# PG13__REGS_MANAGER.net
KiCad netlist of a schematic drawn in Altium Designer
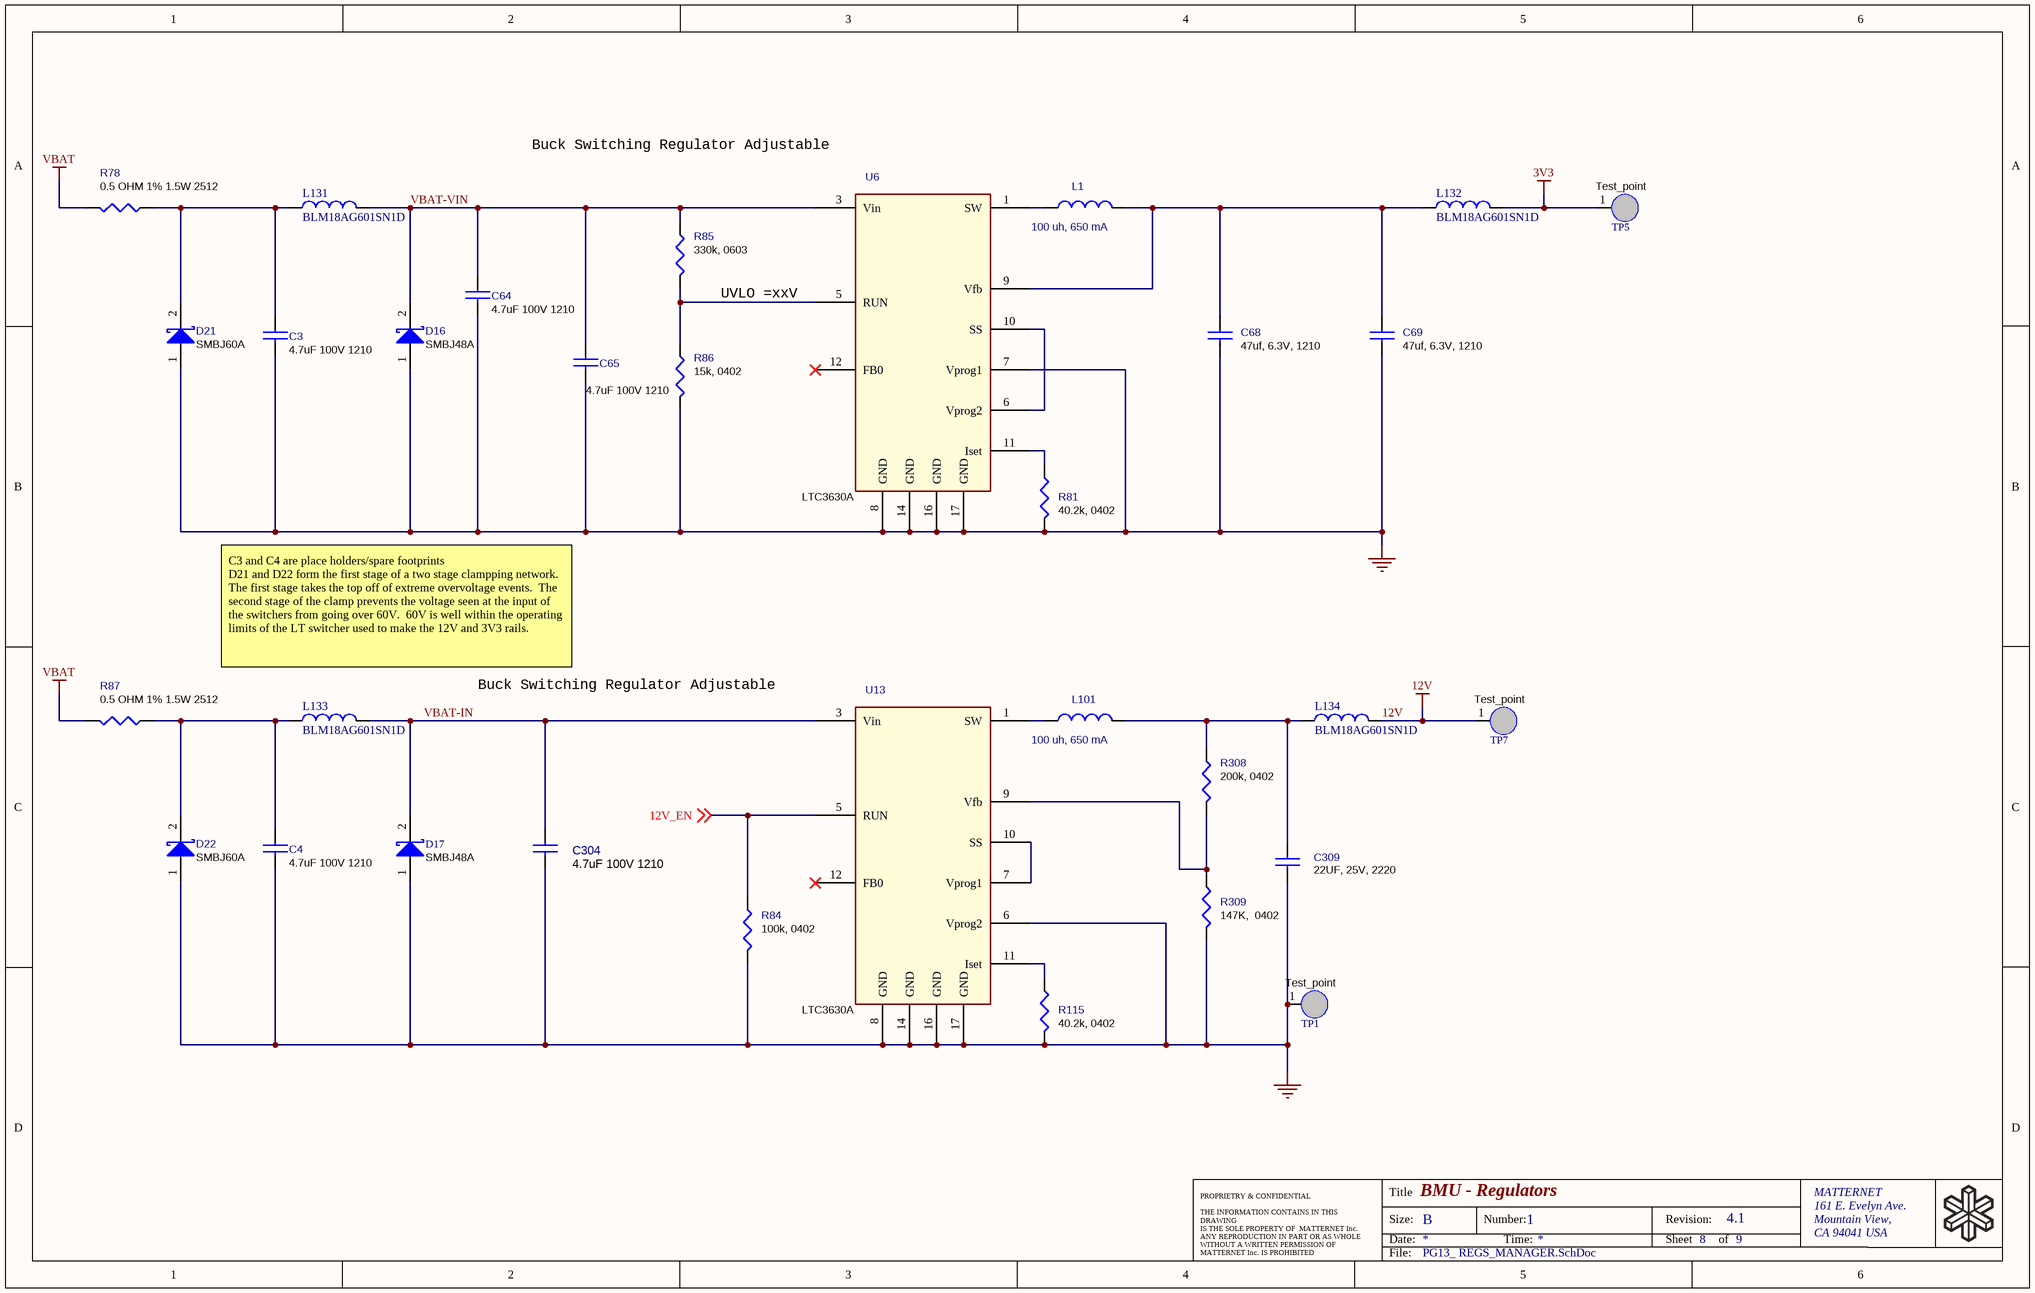
[diagram p0: PG13_ REGS_MANAGER.SchDoc]

(export (version "E")
  (design (tool "Eeschema 10.0.6"))
  (components
    (comp (ref "C3")
      (value "4.7uF 100V 1210")
      (footprint "C1210")
      (description "CAP CER 4.7UF 100V 10% X7S 1210")
      (fields
        (field (name "MANUFACTURER") "TDK")
        (field (name "MANUFACTURER PART NUMBER") "CGA6M3X7S2A475K200AE")
      )
      (libsource (lib "*") (part "CAP-GENERIC"))
    )
    (comp (ref "C4")
      (value "4.7uF 100V 1210")
      (footprint "C1210")
      (description "CAP CER 4.7UF 100V 10% X7S 1210")
      (fields
        (field (name "MANUFACTURER") "TDK")
        (field (name "MANUFACTURER PART NUMBER") "CGA6M3X7S2A475K200AE")
      )
      (libsource (lib "*") (part "CAP-GENERIC"))
    )
    (comp (ref "C64")
      (value "4.7uF 100V 1210")
      (footprint "C1210")
      (description "CAP CER 4.7UF 100V 10% X7S 1210")
      (fields
        (field (name "MANUFACTURER") "TDK")
        (field (name "MANUFACTURER PART NUMBER") "CGA6M3X7S2A475K200AE")
      )
      (libsource (lib "*") (part "CAP-GENERIC"))
    )
    (comp (ref "C65")
      (value "4.7uF 100V 1210")
      (footprint "C1210")
      (description "CAP CER 4.7UF 100V 10% X7S 1210")
      (fields
        (field (name "MANUFACTURER") "TDK")
        (field (name "MANUFACTURER PART NUMBER") "CGA6M3X7S2A475K200AE")
      )
      (libsource (lib "*") (part "CAP-GENERIC"))
    )
    (comp (ref "C68")
      (value "47uf, 6.3V, 1210")
      (footprint "C1210_N")
      (description "CAP CER 47UF 6.3V X7R 1210")
      (fields
        (field (name "MANUFACTURER") "Murata")
        (field (name "MANUFACTURER PART NUMBER") "GCJ32ER70J476KE01L")
      )
      (libsource (lib "*") (part "CAP-Generic-1206"))
    )
    (comp (ref "C69")
      (value "47uf, 6.3V, 1210")
      (footprint "C1210_N")
      (description "CAP CER 47UF 6.3V X7R 1210")
      (fields
        (field (name "MANUFACTURER") "Murata")
        (field (name "MANUFACTURER PART NUMBER") "GCJ32ER70J476KE01L")
      )
      (libsource (lib "*") (part "CAP-Generic-1206"))
    )
    (comp (ref "C304")
      (value "4.7uF 100V 1210")
      (footprint "C1210")
      (description "CAP CER 4.7UF 100V 10% X7S 1210")
      (fields
        (field (name "MANUFACTURER") "TDK")
        (field (name "MANUFACTURER PART NUMBER") "CGA6M3X7S2A475K200AE")
      )
      (libsource (lib "*") (part "CAP-GENERIC"))
    )
    (comp (ref "C309")
      (value "22UF, 25V, 2220")
      (footprint "C2220")
      (description "CAP CER 22UF 25V 10% X7R 2220")
      (fields
        (field (name "MANUFACTURER") "KEMET")
        (field (name "MANUFACTURER PART NUMBER") "C2220X226K3RACAUTO")
      )
      (libsource (lib "*") (part "CAP-GENERIC"))
    )
    (comp (ref "D16")
      (value "SMBJ48A")
      (footprint "DO-214AA")
      (description "Diode TVS Single Uni-Directional 48V 600W 2-Pin DO-214AA")
      (libsource (lib "M2_V8_BMU_V1.0") (part "SMBJ60A"))
    )
    (comp (ref "D17")
      (value "SMBJ48A")
      (footprint "DO-214AA")
      (description "Diode TVS Single Uni-Directional 48V 600W 2-Pin DO-214AA")
      (libsource (lib "M2_V8_BMU_V1.0") (part "SMBJ60A"))
    )
    (comp (ref "D21")
      (value "SMBJ60A")
      (footprint "DO-214AA")
      (libsource (lib "M2_V8_BMU_V1.0") (part "SMBJ60A"))
    )
    (comp (ref "D22")
      (value "SMBJ60A")
      (footprint "DO-214AA")
      (fields
        (field (name "MANUFACTURER") "Vishay Semiconductors")
        (field (name "MANUFACTURER PART NUMBER") "SMBJ60A-E3/52")
      )
      (libsource (lib "M2_V8_BMU_V1.0") (part "SMBJ60A"))
    )
    (comp (ref "L1")
      (value "100 uh, 650 mA")
      (footprint "IND_SRR7045")
      (description "FIXED IND 100UH 650MA 300 MOHM")
      (fields (field (name "MANUFACTURER") "Bourns") (field (name "MANUFACTURER PART NUMBER") "SRR7045-101M"))
      (libsource (lib "*") (part "IND-GENERIC"))
    )
    (comp (ref "L101")
      (value "100 uh, 650 mA")
      (footprint "IND_SRR7045")
      (description "FIXED IND 100UH 650MA 300 MOHM")
      (fields (field (name "MANUFACTURER") "Bourns") (field (name "MANUFACTURER PART NUMBER") "SRR7045-101M"))
      (libsource (lib "*") (part "IND-GENERIC"))
    )
    (comp (ref "L131")
      (value "BLM18AG601SN1D")
      (footprint "INDC1608X10N")
      (description "FERRITE BEAD 600 OHM 0603 1LN")
      (libsource (lib "Altium") (part "BLM18AG601SN1D"))
    )
    (comp (ref "L132")
      (value "BLM18AG601SN1D")
      (footprint "INDC1608X10N")
      (description "FERRITE BEAD 600 OHM 0603 1LN")
      (libsource (lib "Altium") (part "BLM18AG601SN1D"))
    )
    (comp (ref "L133")
      (value "BLM18AG601SN1D")
      (footprint "INDC1608X10N")
      (description "FERRITE BEAD 600 OHM 0603 1LN")
      (libsource (lib "Altium") (part "BLM18AG601SN1D"))
    )
    (comp (ref "L134")
      (value "BLM18AG601SN1D")
      (footprint "INDC1608X10N")
      (description "FERRITE BEAD 600 OHM 0603 1LN")
      (libsource (lib "Altium") (part "BLM18AG601SN1D"))
    )
    (comp (ref "R78")
      (value "0.5 OHM 1% 1.5W 2512")
      (footprint "2512")
      (fields (field (name "TOLERANCE") "1%"))
      (libsource (lib "*") (part "R-Generic"))
    )
    (comp (ref "R81")
      (value "40.2k, 0402")
      (footprint "R0402")
      (description "RES SMD 40.2K OHM 1% 1/16W 0402")
      (fields
        (field (name "MANUFACTURER") "Yageo")
        (field (name "MANUFACTURER PART NUMBER") "RC0402FR-0740K2L")
      )
      (libsource (lib "*") (part "R-Generic-0402"))
    )
    (comp (ref "R84")
      (value "100k, 0402")
      (footprint "R0402")
      (description "RES SMD 100K OHM 1% 1/16W 0402")
      (fields
        (field (name "MANUFACTURER") "Yageo")
        (field (name "MANUFACTURER PART NUMBER") "RC0402FR-07100KL")
      )
      (libsource (lib "*") (part "R-Generic-0402"))
    )
    (comp (ref "R85")
      (value "330k, 0603")
      (footprint "R0603")
      (description "RES SMD 330K OHM 5% 1/10W 0603")
      (fields
        (field (name "MANUFACTURER") "Yageo")
        (field (name "MANUFACTURER PART NUMBER") "RC0603JR-07330KL")
      )
      (libsource (lib "*") (part "R-Generic-0603"))
    )
    (comp (ref "R86")
      (value "15k, 0402")
      (footprint "R0402")
      (description "RES SMD 15K OHM 1% 1/16W 0402")
      (fields
        (field (name "MANUFACTURER") "Yageo")
        (field (name "MANUFACTURER PART NUMBER") "RC0402FR-0715KL")
      )
      (libsource (lib "*") (part "R-Generic-0402"))
    )
    (comp (ref "R87")
      (value "0.5 OHM 1% 1.5W 2512")
      (footprint "2512")
      (fields (field (name "TOLERANCE") "1%"))
      (libsource (lib "*") (part "R-Generic"))
    )
    (comp (ref "R115")
      (value "40.2k, 0402")
      (footprint "R0402")
      (description "RES SMD 40.2K OHM 1% 1/16W 0402")
      (fields
        (field (name "MANUFACTURER") "Yageo")
        (field (name "MANUFACTURER PART NUMBER") "RC0402FR-0740K2L")
      )
      (libsource (lib "*") (part "R-Generic-0402"))
    )
    (comp (ref "R308")
      (value "200k, 0402")
      (footprint "R0402")
      (description "RES SMD 200K OHM 1% 1/16W 0402")
      (fields
        (field (name "MANUFACTURER") "Yageo")
        (field (name "MANUFACTURER PART NUMBER") "RC0402FR-07200KL")
      )
      (libsource (lib "*") (part "R-Generic-0402"))
    )
    (comp (ref "R309")
      (value "147K,  0402")
      (footprint "R0402")
      (description "RES SMD 147K OHM 1% 1/16W 0402")
      (fields
        (field (name "MANUFACTURER") "Yageo")
        (field (name "MANUFACTURER PART NUMBER") "RC0402FR-07147KL")
      )
      (libsource (lib "*") (part "R-Generic-0402"))
    )
    (comp (ref "TP1")
      (value "Test_point")
      (footprint "TP")
      (libsource (lib "M2_V8_BMU_V1.0") (part "Test_point"))
    )
    (comp (ref "TP5")
      (value "Test_point")
      (footprint "TP")
      (libsource (lib "M2_V8_BMU_V1.0") (part "Test_point"))
    )
    (comp (ref "TP7")
      (value "Test_point")
      (footprint "TP")
      (libsource (lib "M2_V8_BMU_V1.0") (part "Test_point"))
    )
    (comp (ref "U6")
      (value "LTC3630A")
      (footprint "LTC3630A")
      (description "IC REG BUCK INV 0.5A SYNC 16MSOP")
      (fields
        (field (name "MANUFACTURER") "Analog Devices / Linear Technology")
        (field (name "MANUFACTURER PART NUMBER") "LTC3630AIMSE#TRPBF")
      )
      (libsource (lib "M2_V8_BMU_V1.0") (part "LTC3630A"))
    )
    (comp (ref "U13")
      (value "LTC3630A")
      (footprint "LTC3630A")
      (description "IC REG BUCK INV 0.5A SYNC 16MSOP")
      (fields
        (field (name "MANUFACTURER") "Analog Devices / Linear Technology")
        (field (name "MANUFACTURER PART NUMBER") "LTC3630AIMSE#TRPBF")
      )
      (libsource (lib "M2_V8_BMU_V1.0") (part "LTC3630A"))
    )
  )
  (nets
    (net (code "1") (name "/VBAT-IN") (class "Default")
      (node (ref "C304") (pin "1") (pinfunction "1_1") (pintype "passive"))
      (node (ref "D17") (pin "2") (pinfunction "K_2") (pintype "passive"))
      (node (ref "L133") (pin "2") (pinfunction "2_2") (pintype "passive"))
      (node (ref "U13") (pin "3") (pinfunction "Vin_3") (pintype "power_in"))
    )
    (net (code "2") (name "/VBAT-VIN") (class "Default")
      (node (ref "C64") (pin "1") (pinfunction "1_1") (pintype "passive"))
      (node (ref "C65") (pin "1") (pinfunction "1_1") (pintype "passive"))
      (node (ref "D16") (pin "2") (pinfunction "K_2") (pintype "passive"))
      (node (ref "L131") (pin "2") (pinfunction "2_2") (pintype "passive"))
      (node (ref "R85") (pin "1") (pinfunction "1_1") (pintype "passive"))
      (node (ref "U6") (pin "3") (pinfunction "Vin_3") (pintype "power_in"))
    )
    (net (code "3") (name "3V3") (class "Default")
      (node (ref "L132") (pin "2") (pinfunction "2_2") (pintype "passive"))
      (node (ref "TP5") (pin "1") (pinfunction "1_1") (pintype "passive"))
    )
    (net (code "4") (name "12V") (class "Default")
      (node (ref "L134") (pin "2") (pinfunction "2_2") (pintype "passive"))
      (node (ref "TP7") (pin "1") (pinfunction "1_1") (pintype "passive"))
    )
    (net (code "5") (name "12V_EN") (class "Default")
      (node (ref "R84") (pin "1") (pinfunction "1_1") (pintype "passive"))
      (node (ref "U13") (pin "5") (pinfunction "RUN_5") (pintype "passive"))
    )
    (net (code "6") (name "GND") (class "Default")
      (node (ref "C3") (pin "2") (pinfunction "2_2") (pintype "passive"))
      (node (ref "C304") (pin "2") (pinfunction "2_2") (pintype "passive"))
      (node (ref "C309") (pin "2") (pinfunction "2_2") (pintype "passive"))
      (node (ref "C4") (pin "2") (pinfunction "2_2") (pintype "passive"))
      (node (ref "C64") (pin "2") (pinfunction "2_2") (pintype "passive"))
      (node (ref "C65") (pin "2") (pinfunction "2_2") (pintype "passive"))
      (node (ref "C68") (pin "2") (pinfunction "2_2") (pintype "passive"))
      (node (ref "C69") (pin "2") (pinfunction "2_2") (pintype "passive"))
      (node (ref "D16") (pin "1") (pinfunction "A_1") (pintype "passive"))
      (node (ref "D17") (pin "1") (pinfunction "A_1") (pintype "passive"))
      (node (ref "D21") (pin "1") (pinfunction "A_1") (pintype "passive"))
      (node (ref "D22") (pin "1") (pinfunction "A_1") (pintype "passive"))
      (node (ref "R115") (pin "2") (pinfunction "2_2") (pintype "passive"))
      (node (ref "R309") (pin "2") (pinfunction "2_2") (pintype "passive"))
      (node (ref "R81") (pin "2") (pinfunction "2_2") (pintype "passive"))
      (node (ref "R84") (pin "2") (pinfunction "2_2") (pintype "passive"))
      (node (ref "R86") (pin "2") (pinfunction "2_2") (pintype "passive"))
      (node (ref "TP1") (pin "1") (pinfunction "1_1") (pintype "passive"))
      (node (ref "U13") (pin "14") (pinfunction "GND_14") (pintype "passive"))
      (node (ref "U13") (pin "16") (pinfunction "GND_16") (pintype "passive"))
      (node (ref "U13") (pin "17") (pinfunction "GND_17") (pintype "passive"))
      (node (ref "U13") (pin "6") (pinfunction "Vprog2_6") (pintype "passive"))
      (node (ref "U13") (pin "8") (pinfunction "GND_8") (pintype "passive"))
      (node (ref "U6") (pin "14") (pinfunction "GND_14") (pintype "passive"))
      (node (ref "U6") (pin "16") (pinfunction "GND_16") (pintype "passive"))
      (node (ref "U6") (pin "17") (pinfunction "GND_17") (pintype "passive"))
      (node (ref "U6") (pin "7") (pinfunction "Vprog1_7") (pintype "passive"))
      (node (ref "U6") (pin "8") (pinfunction "GND_8") (pintype "passive"))
    )
    (net (code "7") (name "Net-(C309-Pad1)") (class "Default")
      (node (ref "C309") (pin "1") (pinfunction "1_1") (pintype "passive"))
      (node (ref "L101") (pin "2") (pinfunction "2_2") (pintype "passive"))
      (node (ref "L134") (pin "1") (pinfunction "1_1") (pintype "passive"))
      (node (ref "R308") (pin "1") (pinfunction "1_1") (pintype "passive"))
    )
    (net (code "8") (name "Net-(D21-K)") (class "Default")
      (node (ref "C3") (pin "1") (pinfunction "1_1") (pintype "passive"))
      (node (ref "D21") (pin "2") (pinfunction "K_2") (pintype "passive"))
      (node (ref "L131") (pin "1") (pinfunction "1_1") (pintype "passive"))
      (node (ref "R78") (pin "1") (pinfunction "1_1") (pintype "passive"))
    )
    (net (code "9") (name "Net-(D22-K)") (class "Default")
      (node (ref "C4") (pin "1") (pinfunction "1_1") (pintype "passive"))
      (node (ref "D22") (pin "2") (pinfunction "K_2") (pintype "passive"))
      (node (ref "L133") (pin "1") (pinfunction "1_1") (pintype "passive"))
      (node (ref "R87") (pin "1") (pinfunction "1_1") (pintype "passive"))
    )
    (net (code "10") (name "Net-(U6-Iset)") (class "Default")
      (node (ref "R81") (pin "1") (pinfunction "1_1") (pintype "passive"))
      (node (ref "U6") (pin "11") (pinfunction "Iset_11") (pintype "passive"))
    )
    (net (code "11") (name "Net-(U6-RUN)") (class "Default")
      (node (ref "R85") (pin "2") (pinfunction "2_2") (pintype "passive"))
      (node (ref "R86") (pin "1") (pinfunction "1_1") (pintype "passive"))
      (node (ref "U6") (pin "5") (pinfunction "RUN_5") (pintype "passive"))
    )
    (net (code "12") (name "Net-(U6-SS)") (class "Default")
      (node (ref "U6") (pin "10") (pinfunction "SS_10") (pintype "passive"))
      (node (ref "U6") (pin "6") (pinfunction "Vprog2_6") (pintype "passive"))
    )
    (net (code "13") (name "Net-(U6-SW)") (class "Default")
      (node (ref "L1") (pin "1") (pinfunction "1_1") (pintype "passive"))
      (node (ref "U6") (pin "1") (pinfunction "SW_1") (pintype "passive"))
    )
    (net (code "14") (name "Net-(U6-Vfb)") (class "Default")
      (node (ref "C68") (pin "1") (pinfunction "1_1") (pintype "passive"))
      (node (ref "C69") (pin "1") (pinfunction "1_1") (pintype "passive"))
      (node (ref "L1") (pin "2") (pinfunction "2_2") (pintype "passive"))
      (node (ref "L132") (pin "1") (pinfunction "1_1") (pintype "passive"))
      (node (ref "U6") (pin "9") (pinfunction "Vfb_9") (pintype "passive"))
    )
    (net (code "15") (name "Net-(U13-Iset)") (class "Default")
      (node (ref "R115") (pin "1") (pinfunction "1_1") (pintype "passive"))
      (node (ref "U13") (pin "11") (pinfunction "Iset_11") (pintype "passive"))
    )
    (net (code "16") (name "Net-(U13-SS)") (class "Default")
      (node (ref "U13") (pin "10") (pinfunction "SS_10") (pintype "passive"))
      (node (ref "U13") (pin "7") (pinfunction "Vprog1_7") (pintype "passive"))
    )
    (net (code "17") (name "Net-(U13-SW)") (class "Default")
      (node (ref "L101") (pin "1") (pinfunction "1_1") (pintype "passive"))
      (node (ref "U13") (pin "1") (pinfunction "SW_1") (pintype "passive"))
    )
    (net (code "18") (name "Net-(U13-Vfb)") (class "Default")
      (node (ref "R308") (pin "2") (pinfunction "2_2") (pintype "passive"))
      (node (ref "R309") (pin "1") (pinfunction "1_1") (pintype "passive"))
      (node (ref "U13") (pin "9") (pinfunction "Vfb_9") (pintype "passive"))
    )
    (net (code "19") (name "VBAT") (class "Default")
      (node (ref "R78") (pin "2") (pinfunction "2_2") (pintype "passive"))
      (node (ref "R87") (pin "2") (pinfunction "2_2") (pintype "passive"))
    )
    (net (code "20") (name "unconnected-(U6-FB0-Pad12)") (class "Default")
      (node (ref "U6") (pin "12") (pinfunction "FB0_12") (pintype "passive+no_connect"))
    )
    (net (code "21") (name "unconnected-(U13-FB0-Pad12)") (class "Default")
      (node (ref "U13") (pin "12") (pinfunction "FB0_12") (pintype "passive+no_connect"))
    )
  )
)
